# ChipPlatine.net
KiCad netlist of a schematic drawn in EAGLE
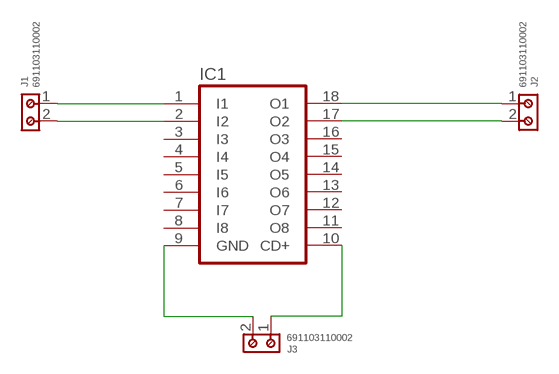
[diagram p0: schematic, sheet 1]

(export (version "E")
  (design (tool "Eeschema 10.0.6"))
  (components
    (comp (ref "IC1")
      (value "ULN2803A")
      (footprint "eagle-import:DIL18")
      (libsource (lib "eagle-import") (part "ULN2803A"))
    )
    (comp (ref "J1")
      (value "691103110002")
      (footprint "eagle-import:691103110002")
      (libsource (lib "eagle-import") (part "691103110002"))
    )
    (comp (ref "J2")
      (value "691103110002")
      (footprint "eagle-import:691103110002")
      (libsource (lib "eagle-import") (part "691103110002"))
    )
    (comp (ref "J3")
      (value "691103110002")
      (footprint "eagle-import:691103110002")
      (libsource (lib "eagle-import") (part "691103110002"))
    )
  )
  (nets
    (net (code "1") (name "Net-(IC1-CD+)") (class "Default")
      (node (ref "IC1") (pin "10") (pinfunction "CD+_10") (pintype "passive"))
      (node (ref "J3") (pin "1") (pinfunction "1_1") (pintype "passive"))
    )
    (net (code "2") (name "Net-(IC1-GND)") (class "Default")
      (node (ref "IC1") (pin "9") (pinfunction "GND_9") (pintype "power_in"))
      (node (ref "J3") (pin "2") (pinfunction "2_2") (pintype "passive"))
    )
    (net (code "3") (name "Net-(IC1-I1)") (class "Default")
      (node (ref "IC1") (pin "1") (pinfunction "I1_1") (pintype "input"))
      (node (ref "J1") (pin "1") (pinfunction "1_1") (pintype "passive"))
    )
    (net (code "4") (name "Net-(IC1-I2)") (class "Default")
      (node (ref "IC1") (pin "2") (pinfunction "I2_2") (pintype "input"))
      (node (ref "J1") (pin "2") (pinfunction "2_2") (pintype "passive"))
    )
    (net (code "5") (name "Net-(IC1-O1)") (class "Default")
      (node (ref "IC1") (pin "18") (pinfunction "O1_18") (pintype "open_collector"))
      (node (ref "J2") (pin "1") (pinfunction "1_1") (pintype "passive"))
    )
    (net (code "6") (name "Net-(IC1-O2)") (class "Default")
      (node (ref "IC1") (pin "17") (pinfunction "O2_17") (pintype "open_collector"))
      (node (ref "J2") (pin "2") (pinfunction "2_2") (pintype "passive"))
    )
    (net (code "7") (name "unconnected-(IC1-I3-Pad3)") (class "Default")
      (node (ref "IC1") (pin "3") (pinfunction "I3_3") (pintype "input"))
    )
    (net (code "8") (name "unconnected-(IC1-I4-Pad4)") (class "Default")
      (node (ref "IC1") (pin "4") (pinfunction "I4_4") (pintype "input"))
    )
    (net (code "9") (name "unconnected-(IC1-I5-Pad5)") (class "Default")
      (node (ref "IC1") (pin "5") (pinfunction "I5_5") (pintype "input"))
    )
    (net (code "10") (name "unconnected-(IC1-I6-Pad6)") (class "Default")
      (node (ref "IC1") (pin "6") (pinfunction "I6_6") (pintype "input"))
    )
    (net (code "11") (name "unconnected-(IC1-I7-Pad7)") (class "Default")
      (node (ref "IC1") (pin "7") (pinfunction "I7_7") (pintype "input"))
    )
    (net (code "12") (name "unconnected-(IC1-I8-Pad8)") (class "Default")
      (node (ref "IC1") (pin "8") (pinfunction "I8_8") (pintype "input"))
    )
    (net (code "13") (name "unconnected-(IC1-O3-Pad16)") (class "Default")
      (node (ref "IC1") (pin "16") (pinfunction "O3_16") (pintype "open_collector"))
    )
    (net (code "14") (name "unconnected-(IC1-O4-Pad15)") (class "Default")
      (node (ref "IC1") (pin "15") (pinfunction "O4_15") (pintype "open_collector"))
    )
    (net (code "15") (name "unconnected-(IC1-O5-Pad14)") (class "Default")
      (node (ref "IC1") (pin "14") (pinfunction "O5_14") (pintype "open_collector"))
    )
    (net (code "16") (name "unconnected-(IC1-O6-Pad13)") (class "Default")
      (node (ref "IC1") (pin "13") (pinfunction "O6_13") (pintype "open_collector"))
    )
    (net (code "17") (name "unconnected-(IC1-O7-Pad12)") (class "Default")
      (node (ref "IC1") (pin "12") (pinfunction "O7_12") (pintype "open_collector"))
    )
    (net (code "18") (name "unconnected-(IC1-O8-Pad11)") (class "Default")
      (node (ref "IC1") (pin "11") (pinfunction "O8_11") (pintype "open_collector"))
    )
  )
)
